# Steering_IOSch.net
KiCad netlist of a schematic drawn in Altium Designer
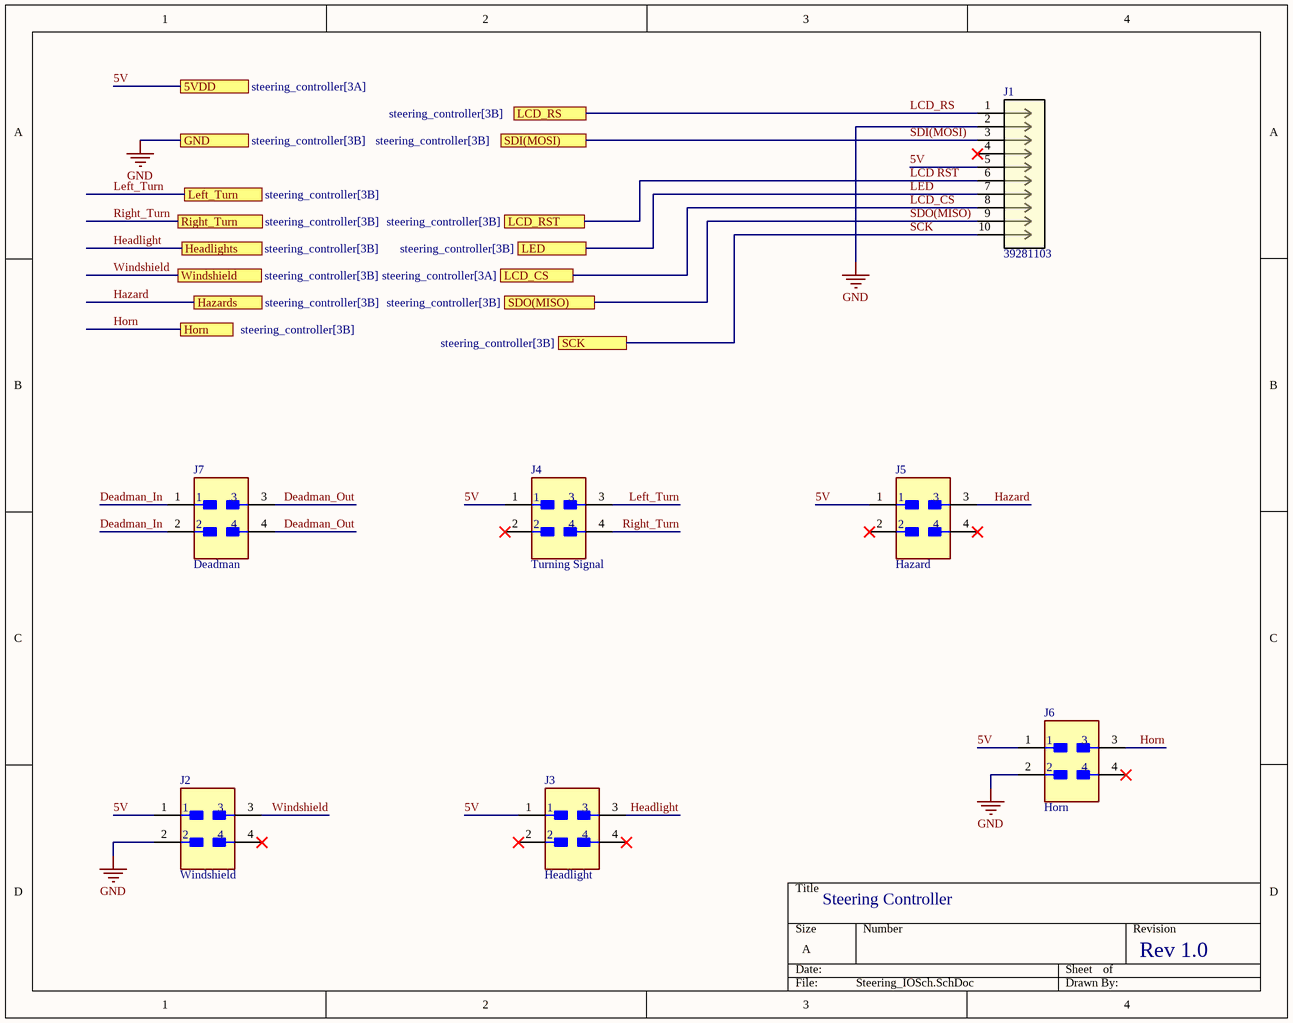
[diagram p0: Steering_IOSch.SchDoc]

(export (version "E")
  (design (tool "Eeschema 10.0.6"))
  (components
    (comp (ref "J1")
      (value "39281103")
      (footprint "CON_39281103")
      (description "No Description Available")
      (libsource (lib "asib") (part "39281103"))
    )
    (comp (ref "J2")
      (value "Windshield")
      (footprint "asib:FP-0039281043-MFG")
      (description "CONN HEADER VERT 4POS 4.2MM. 0039281043")
      (fields (field (name "MANUFACTURER PART NUMBER") "0039281043") (field (name "MANUFACTURER") "Molex"))
      (libsource (lib "asib") (part "1x4_FEMALE_POWER"))
    )
    (comp (ref "J3")
      (value "Headlight")
      (footprint "asib:FP-0039281043-MFG")
      (description "CONN HEADER VERT 4POS 4.2MM. 0039281043")
      (fields (field (name "MANUFACTURER PART NUMBER") "0039281043") (field (name "MANUFACTURER") "Molex"))
      (libsource (lib "asib") (part "1x4_FEMALE_POWER"))
    )
    (comp (ref "J4")
      (value "Turning Signal")
      (footprint "asib:FP-0039281043-MFG")
      (description "CONN HEADER VERT 4POS 4.2MM. 0039281043")
      (fields (field (name "MANUFACTURER PART NUMBER") "0039281043") (field (name "MANUFACTURER") "Molex"))
      (libsource (lib "asib") (part "1x4_FEMALE_POWER"))
    )
    (comp (ref "J5")
      (value "Hazard")
      (footprint "asib:FP-0039281043-MFG")
      (description "CONN HEADER VERT 4POS 4.2MM. 0039281043")
      (fields (field (name "MANUFACTURER PART NUMBER") "0039281043") (field (name "MANUFACTURER") "Molex"))
      (libsource (lib "asib") (part "1x4_FEMALE_POWER"))
    )
    (comp (ref "J6")
      (value "Horn")
      (footprint "asib:FP-0039281043-MFG")
      (description "CONN HEADER VERT 4POS 4.2MM. 0039281043")
      (fields (field (name "MANUFACTURER PART NUMBER") "0039281043") (field (name "MANUFACTURER") "Molex"))
      (libsource (lib "asib") (part "1x4_FEMALE_POWER"))
    )
    (comp (ref "J7")
      (value "Deadman")
      (footprint "asib:FP-0039281043-MFG")
      (description "CONN HEADER VERT 4POS 4.2MM. 0039281043")
      (fields (field (name "MANUFACTURER PART NUMBER") "0039281043") (field (name "MANUFACTURER") "Molex"))
      (libsource (lib "asib") (part "1x4_FEMALE_POWER"))
    )
  )
  (nets
    (net (code "1") (name "/5V") (class "Default")
      (node (ref "J1") (pin "5") (pinfunction "5_5") (pintype "passive"))
      (node (ref "J2") (pin "1") (pinfunction "1_1") (pintype "passive"))
      (node (ref "J3") (pin "1") (pinfunction "1_1") (pintype "passive"))
      (node (ref "J4") (pin "1") (pinfunction "1_1") (pintype "passive"))
      (node (ref "J5") (pin "1") (pinfunction "1_1") (pintype "passive"))
      (node (ref "J6") (pin "1") (pinfunction "1_1") (pintype "passive"))
    )
    (net (code "2") (name "/Deadman_In") (class "Default")
      (node (ref "J7") (pin "1") (pinfunction "1_1") (pintype "passive"))
      (node (ref "J7") (pin "2") (pinfunction "2_2") (pintype "passive"))
    )
    (net (code "3") (name "/Deadman_Out") (class "Default")
      (node (ref "J7") (pin "3") (pinfunction "3_3") (pintype "passive"))
      (node (ref "J7") (pin "4") (pinfunction "4_4") (pintype "passive"))
    )
    (net (code "4") (name "/Hazard") (class "Default")
      (node (ref "J5") (pin "3") (pinfunction "3_3") (pintype "passive"))
    )
    (net (code "5") (name "/Headlight") (class "Default")
      (node (ref "J3") (pin "3") (pinfunction "3_3") (pintype "passive"))
    )
    (net (code "6") (name "/Horn") (class "Default")
      (node (ref "J6") (pin "3") (pinfunction "3_3") (pintype "passive"))
    )
    (net (code "7") (name "/LCD RST") (class "Default")
      (node (ref "J1") (pin "6") (pinfunction "6_6") (pintype "passive"))
    )
    (net (code "8") (name "/LCD_CS") (class "Default")
      (node (ref "J1") (pin "8") (pinfunction "8_8") (pintype "passive"))
    )
    (net (code "9") (name "/LCD_RS") (class "Default")
      (node (ref "J1") (pin "1") (pinfunction "1_1") (pintype "passive"))
    )
    (net (code "10") (name "/LED") (class "Default")
      (node (ref "J1") (pin "7") (pinfunction "7_7") (pintype "passive"))
    )
    (net (code "11") (name "/Left_Turn") (class "Default")
      (node (ref "J4") (pin "3") (pinfunction "3_3") (pintype "passive"))
    )
    (net (code "12") (name "/Right_Turn") (class "Default")
      (node (ref "J4") (pin "4") (pinfunction "4_4") (pintype "passive"))
    )
    (net (code "13") (name "/SCK") (class "Default")
      (node (ref "J1") (pin "10") (pinfunction "10_10") (pintype "passive"))
    )
    (net (code "14") (name "/SDI(MOSI)") (class "Default")
      (node (ref "J1") (pin "3") (pinfunction "3_3") (pintype "passive"))
    )
    (net (code "15") (name "/SDO(MISO)") (class "Default")
      (node (ref "J1") (pin "9") (pinfunction "9_9") (pintype "passive"))
    )
    (net (code "16") (name "/Windshield") (class "Default")
      (node (ref "J2") (pin "3") (pinfunction "3_3") (pintype "passive"))
    )
    (net (code "17") (name "GND") (class "Default")
      (node (ref "J1") (pin "2") (pinfunction "2_2") (pintype "passive"))
      (node (ref "J2") (pin "2") (pinfunction "2_2") (pintype "passive"))
      (node (ref "J6") (pin "2") (pinfunction "2_2") (pintype "passive"))
    )
    (net (code "18") (name "unconnected-(J1-Pad4)") (class "Default")
      (node (ref "J1") (pin "4") (pinfunction "4_4") (pintype "passive+no_connect"))
    )
    (net (code "19") (name "unconnected-(J2-Pad4)") (class "Default")
      (node (ref "J2") (pin "4") (pinfunction "4_4") (pintype "passive+no_connect"))
    )
    (net (code "20") (name "unconnected-(J3-Pad2)") (class "Default")
      (node (ref "J3") (pin "2") (pinfunction "2_2") (pintype "passive+no_connect"))
    )
    (net (code "21") (name "unconnected-(J3-Pad4)") (class "Default")
      (node (ref "J3") (pin "4") (pinfunction "4_4") (pintype "passive+no_connect"))
    )
    (net (code "22") (name "unconnected-(J4-Pad2)") (class "Default")
      (node (ref "J4") (pin "2") (pinfunction "2_2") (pintype "passive+no_connect"))
    )
    (net (code "23") (name "unconnected-(J5-Pad2)") (class "Default")
      (node (ref "J5") (pin "2") (pinfunction "2_2") (pintype "passive+no_connect"))
    )
    (net (code "24") (name "unconnected-(J5-Pad4)") (class "Default")
      (node (ref "J5") (pin "4") (pinfunction "4_4") (pintype "passive+no_connect"))
    )
    (net (code "25") (name "unconnected-(J6-Pad4)") (class "Default")
      (node (ref "J6") (pin "4") (pinfunction "4_4") (pintype "passive+no_connect"))
    )
  )
)
